# Power_Supply.net
KiCad netlist of a schematic drawn in Altium Designer
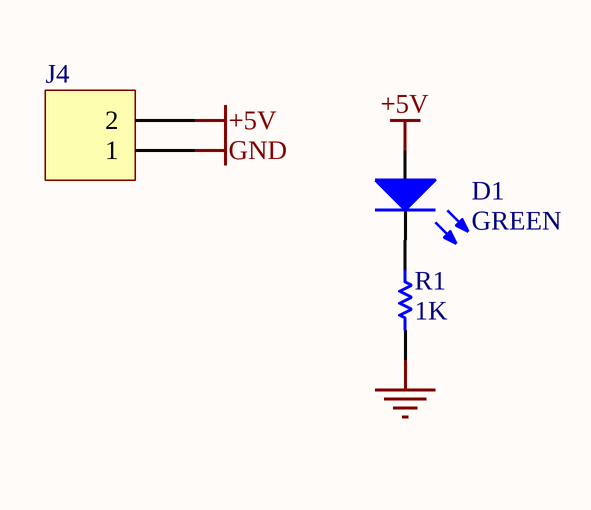
[diagram p0: Power Supply.SchDoc]

(export (version "E")
  (design (tool "Eeschema 10.0.6"))
  (components
    (comp (ref "D1")
      (value "GREEN")
      (footprint "LED-5mm_Red")
      (description "Typical INFRARED GaAs LED")
      (fields (field (name "MANUFACTURER") "Generic Components") (field (name "PUBLISHER") "Altium Limited"))
      (libsource (lib "Miscellaneous Devices") (part "LED"))
    )
    (comp (ref "J4")
      (value "2PIN")
      (footprint "HDR1X2")
      (description "Header, 2-Pin")
      (fields (field (name "MANUFACTURER") "Generic Components") (field (name "PUBLISHER") "Altium Limited"))
      (libsource (lib "Miscellaneous Connectors") (part "Header 2"))
    )
    (comp (ref "R1")
      (value "1K")
      (footprint "0805")
      (description "Resistor")
      (fields (field (name "PUBLISHER") "Altium Limited"))
      (libsource (lib "Miscellaneous Devices") (part "Res1"))
    )
  )
  (nets
    (net (code "1") (name "+5V") (class "Default")
      (node (ref "D1") (pin "1") (pinfunction "A_1") (pintype "passive"))
      (node (ref "J4") (pin "2") (pinfunction "2_2") (pintype "passive"))
    )
    (net (code "2") (name "GND") (class "Default")
      (node (ref "J4") (pin "1") (pinfunction "1_1") (pintype "passive"))
      (node (ref "R1") (pin "2") (pinfunction "2_2") (pintype "passive"))
    )
    (net (code "3") (name "Net-(D1-K)") (class "Default")
      (node (ref "D1") (pin "2") (pinfunction "K_2") (pintype "passive"))
      (node (ref "R1") (pin "1") (pinfunction "1_1") (pintype "passive"))
    )
  )
)
